# Power_Button.net
KiCad netlist of a schematic drawn in EAGLE
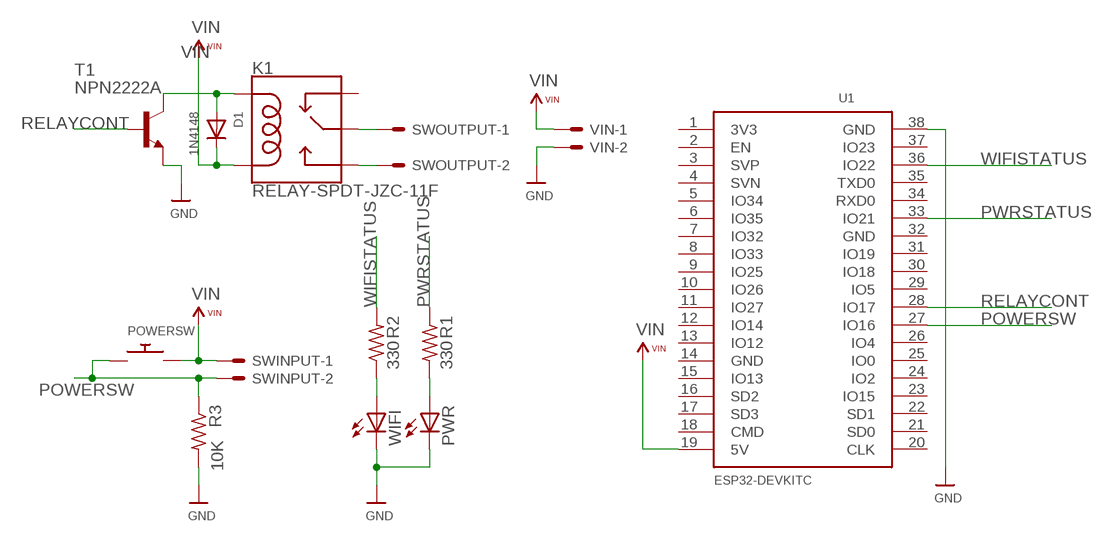
[diagram p0: schematic, sheet 1]

(export (version "E")
  (design (tool "Eeschema 10.0.6"))
  (components
    (comp (ref "D1")
      (value "1N4148")
      (footprint "eagle-import:DO-1N4148")
      (libsource (lib "eagle-import") (part "DIODEDO-1N4148"))
    )
    (comp (ref "K1")
      (value "RELAY-SPDT-JZC-11F")
      (footprint "eagle-import:RELAY-JZC")
      (libsource (lib "eagle-import") (part "RELAY-SPDT-JZC-11F"))
    )
    (comp (ref "POWERSW")
      (value "SWITCH_PUSHBUTTONEVQ-PE")
      (footprint "eagle-import:TACT_PANA-EVQ")
      (libsource (lib "eagle-import") (part "SWITCH_PUSHBUTTONEVQ-PE"))
    )
    (comp (ref "PWR")
      (value "LEDCHIPLED_1206")
      (footprint "eagle-import:CHIPLED_1206")
      (libsource (lib "eagle-import") (part "LEDCHIPLED_1206"))
    )
    (comp (ref "R1")
      (value "330")
      (footprint "eagle-import:M1206")
      (libsource (lib "eagle-import") (part "R-US_M1206"))
    )
    (comp (ref "R2")
      (value "330")
      (footprint "eagle-import:M1206")
      (libsource (lib "eagle-import") (part "R-US_M1206"))
    )
    (comp (ref "R3")
      (value "10K")
      (footprint "eagle-import:M1206")
      (libsource (lib "eagle-import") (part "R-US_M1206"))
    )
    (comp (ref "SWINPUT")
      (value "KK-156-2")
      (footprint "eagle-import:KK-156-2")
      (fields (field (name "MF") "MOLEX"))
      (libsource (lib "eagle-import") (part "KK-156-2"))
    )
    (comp (ref "SWOUTPUT")
      (value "KK-156-2")
      (footprint "eagle-import:KK-156-2")
      (fields (field (name "MF") "MOLEX"))
      (libsource (lib "eagle-import") (part "KK-156-2"))
    )
    (comp (ref "T1")
      (value "NPN2222A")
      (footprint "eagle-import:TO92")
      (libsource (lib "eagle-import") (part "2N5088"))
    )
    (comp (ref "U1")
      (value "ESP32DEVKITC")
      (footprint "eagle-import:ESP32-DEVKITC")
      (libsource (lib "eagle-import") (part "ESP32DEVKITC"))
    )
    (comp (ref "VIN")
      (value "KK-156-2")
      (footprint "eagle-import:KK-156-2")
      (fields (field (name "MF") "MOLEX"))
      (libsource (lib "eagle-import") (part "KK-156-2"))
    )
    (comp (ref "WIFI")
      (value "LEDCHIPLED_1206")
      (footprint "eagle-import:CHIPLED_1206")
      (libsource (lib "eagle-import") (part "LEDCHIPLED_1206"))
    )
  )
  (nets
    (net (code "1") (name "/POWERSW") (class "Default")
      (node (ref "POWERSW") (pin "P$1") (pinfunction "P$1_P$1") (pintype "passive"))
      (node (ref "R3") (pin "1") (pinfunction "1_1") (pintype "passive"))
      (node (ref "SWINPUT") (pin "2") (pinfunction "S_2") (pintype "passive"))
      (node (ref "U1") (pin "27") (pinfunction "IO16_27") (pintype "bidirectional"))
    )
    (net (code "2") (name "/PWRSTATUS") (class "Default")
      (node (ref "R1") (pin "1") (pinfunction "1_1") (pintype "passive"))
      (node (ref "U1") (pin "33") (pinfunction "IO21_33") (pintype "bidirectional"))
    )
    (net (code "3") (name "/RELAYCONT") (class "Default")
      (node (ref "T1") (pin "2") (pinfunction "B_2") (pintype "passive"))
      (node (ref "U1") (pin "28") (pinfunction "IO17_28") (pintype "bidirectional"))
    )
    (net (code "4") (name "/WIFISTATUS") (class "Default")
      (node (ref "R2") (pin "2") (pinfunction "2_2") (pintype "passive"))
      (node (ref "U1") (pin "36") (pinfunction "IO22_36") (pintype "bidirectional"))
    )
    (net (code "5") (name "GND") (class "Default")
      (node (ref "PWR") (pin "C") (pinfunction "C_C") (pintype "passive"))
      (node (ref "R3") (pin "2") (pinfunction "2_2") (pintype "passive"))
      (node (ref "T1") (pin "3") (pinfunction "E_3") (pintype "passive"))
      (node (ref "U1") (pin "38") (pinfunction "GND_38") (pintype "bidirectional"))
      (node (ref "VIN") (pin "2") (pinfunction "S_2") (pintype "passive"))
      (node (ref "WIFI") (pin "C") (pinfunction "C_C") (pintype "passive"))
    )
    (net (code "6") (name "Net-(K1-COIL1)") (class "Default")
      (node (ref "D1") (pin "A") (pinfunction "A_A") (pintype "passive"))
      (node (ref "K1") (pin "5") (pinfunction "COIL1_5") (pintype "bidirectional"))
      (node (ref "T1") (pin "1") (pinfunction "C_1") (pintype "passive"))
    )
    (net (code "7") (name "Net-(K1-MAIN)") (class "Default")
      (node (ref "K1") (pin "4") (pinfunction "MAIN_4") (pintype "bidirectional"))
      (node (ref "SWOUTPUT") (pin "1") (pinfunction "S_1") (pintype "passive"))
    )
    (net (code "8") (name "Net-(K1-NO)") (class "Default")
      (node (ref "K1") (pin "3") (pinfunction "NO_3") (pintype "bidirectional"))
      (node (ref "SWOUTPUT") (pin "2") (pinfunction "S_2") (pintype "passive"))
    )
    (net (code "9") (name "Net-(PWR-PadA)") (class "Default")
      (node (ref "PWR") (pin "A") (pinfunction "A_A") (pintype "passive"))
      (node (ref "R1") (pin "2") (pinfunction "2_2") (pintype "passive"))
    )
    (net (code "10") (name "Net-(R2-Pad1)") (class "Default")
      (node (ref "R2") (pin "1") (pinfunction "1_1") (pintype "passive"))
      (node (ref "WIFI") (pin "A") (pinfunction "A_A") (pintype "passive"))
    )
    (net (code "11") (name "VIN") (class "Default")
      (node (ref "D1") (pin "C") (pinfunction "C_C") (pintype "passive"))
      (node (ref "K1") (pin "1") (pinfunction "COIL2_1") (pintype "bidirectional"))
      (node (ref "POWERSW") (pin "P$2") (pinfunction "P$2_P$2") (pintype "passive"))
      (node (ref "SWINPUT") (pin "1") (pinfunction "S_1") (pintype "passive"))
      (node (ref "U1") (pin "19") (pinfunction "5V_19") (pintype "bidirectional"))
      (node (ref "VIN") (pin "1") (pinfunction "S_1") (pintype "passive"))
    )
    (net (code "12") (name "unconnected-(K1-NC-Pad2)") (class "Default")
      (node (ref "K1") (pin "2") (pinfunction "NC_2") (pintype "bidirectional"))
    )
    (net (code "13") (name "unconnected-(U1-3V3-Pad1)") (class "Default")
      (node (ref "U1") (pin "1") (pinfunction "3V3_1") (pintype "bidirectional"))
    )
    (net (code "14") (name "unconnected-(U1-CLK-Pad20)") (class "Default")
      (node (ref "U1") (pin "20") (pinfunction "CLK_20") (pintype "bidirectional"))
    )
    (net (code "15") (name "unconnected-(U1-CMD-Pad18)") (class "Default")
      (node (ref "U1") (pin "18") (pinfunction "CMD_18") (pintype "bidirectional"))
    )
    (net (code "16") (name "unconnected-(U1-EN-Pad2)") (class "Default")
      (node (ref "U1") (pin "2") (pinfunction "EN_2") (pintype "bidirectional"))
    )
    (net (code "17") (name "unconnected-(U1-GND-Pad14)") (class "Default")
      (node (ref "U1") (pin "14") (pinfunction "GND_14") (pintype "bidirectional"))
    )
    (net (code "18") (name "unconnected-(U1-GND-Pad32)") (class "Default")
      (node (ref "U1") (pin "32") (pinfunction "GND_32") (pintype "bidirectional"))
    )
    (net (code "19") (name "unconnected-(U1-IO0-Pad25)") (class "Default")
      (node (ref "U1") (pin "25") (pinfunction "IO0_25") (pintype "bidirectional"))
    )
    (net (code "20") (name "unconnected-(U1-IO2-Pad24)") (class "Default")
      (node (ref "U1") (pin "24") (pinfunction "IO2_24") (pintype "bidirectional"))
    )
    (net (code "21") (name "unconnected-(U1-IO4-Pad26)") (class "Default")
      (node (ref "U1") (pin "26") (pinfunction "IO4_26") (pintype "bidirectional"))
    )
    (net (code "22") (name "unconnected-(U1-IO5-Pad29)") (class "Default")
      (node (ref "U1") (pin "29") (pinfunction "IO5_29") (pintype "bidirectional"))
    )
    (net (code "23") (name "unconnected-(U1-IO12-Pad13)") (class "Default")
      (node (ref "U1") (pin "13") (pinfunction "IO12_13") (pintype "bidirectional"))
    )
    (net (code "24") (name "unconnected-(U1-IO13-Pad15)") (class "Default")
      (node (ref "U1") (pin "15") (pinfunction "IO13_15") (pintype "bidirectional"))
    )
    (net (code "25") (name "unconnected-(U1-IO14-Pad12)") (class "Default")
      (node (ref "U1") (pin "12") (pinfunction "IO14_12") (pintype "bidirectional"))
    )
    (net (code "26") (name "unconnected-(U1-IO15-Pad23)") (class "Default")
      (node (ref "U1") (pin "23") (pinfunction "IO15_23") (pintype "bidirectional"))
    )
    (net (code "27") (name "unconnected-(U1-IO18-Pad30)") (class "Default")
      (node (ref "U1") (pin "30") (pinfunction "IO18_30") (pintype "bidirectional"))
    )
    (net (code "28") (name "unconnected-(U1-IO19-Pad31)") (class "Default")
      (node (ref "U1") (pin "31") (pinfunction "IO19_31") (pintype "bidirectional"))
    )
    (net (code "29") (name "unconnected-(U1-IO23-Pad37)") (class "Default")
      (node (ref "U1") (pin "37") (pinfunction "IO23_37") (pintype "bidirectional"))
    )
    (net (code "30") (name "unconnected-(U1-IO25-Pad9)") (class "Default")
      (node (ref "U1") (pin "9") (pinfunction "IO25_9") (pintype "bidirectional"))
    )
    (net (code "31") (name "unconnected-(U1-IO26-Pad10)") (class "Default")
      (node (ref "U1") (pin "10") (pinfunction "IO26_10") (pintype "bidirectional"))
    )
    (net (code "32") (name "unconnected-(U1-IO27-Pad11)") (class "Default")
      (node (ref "U1") (pin "11") (pinfunction "IO27_11") (pintype "bidirectional"))
    )
    (net (code "33") (name "unconnected-(U1-IO32-Pad7)") (class "Default")
      (node (ref "U1") (pin "7") (pinfunction "IO32_7") (pintype "bidirectional"))
    )
    (net (code "34") (name "unconnected-(U1-IO33-Pad8)") (class "Default")
      (node (ref "U1") (pin "8") (pinfunction "IO33_8") (pintype "bidirectional"))
    )
    (net (code "35") (name "unconnected-(U1-IO34-Pad5)") (class "Default")
      (node (ref "U1") (pin "5") (pinfunction "IO34_5") (pintype "bidirectional"))
    )
    (net (code "36") (name "unconnected-(U1-IO35-Pad6)") (class "Default")
      (node (ref "U1") (pin "6") (pinfunction "IO35_6") (pintype "bidirectional"))
    )
    (net (code "37") (name "unconnected-(U1-RXD0-Pad34)") (class "Default")
      (node (ref "U1") (pin "34") (pinfunction "RXD0_34") (pintype "bidirectional"))
    )
    (net (code "38") (name "unconnected-(U1-SD0-Pad21)") (class "Default")
      (node (ref "U1") (pin "21") (pinfunction "SD0_21") (pintype "bidirectional"))
    )
    (net (code "39") (name "unconnected-(U1-SD1-Pad22)") (class "Default")
      (node (ref "U1") (pin "22") (pinfunction "SD1_22") (pintype "bidirectional"))
    )
    (net (code "40") (name "unconnected-(U1-SD2-Pad16)") (class "Default")
      (node (ref "U1") (pin "16") (pinfunction "SD2_16") (pintype "bidirectional"))
    )
    (net (code "41") (name "unconnected-(U1-SD3-Pad17)") (class "Default")
      (node (ref "U1") (pin "17") (pinfunction "SD3_17") (pintype "bidirectional"))
    )
    (net (code "42") (name "unconnected-(U1-SVN-Pad4)") (class "Default")
      (node (ref "U1") (pin "4") (pinfunction "SVN_4") (pintype "bidirectional"))
    )
    (net (code "43") (name "unconnected-(U1-SVP-Pad3)") (class "Default")
      (node (ref "U1") (pin "3") (pinfunction "SVP_3") (pintype "bidirectional"))
    )
    (net (code "44") (name "unconnected-(U1-TXD0-Pad35)") (class "Default")
      (node (ref "U1") (pin "35") (pinfunction "TXD0_35") (pintype "bidirectional"))
    )
  )
)
